# 08_eMMC.net
KiCad netlist of a schematic drawn in Altium Designer
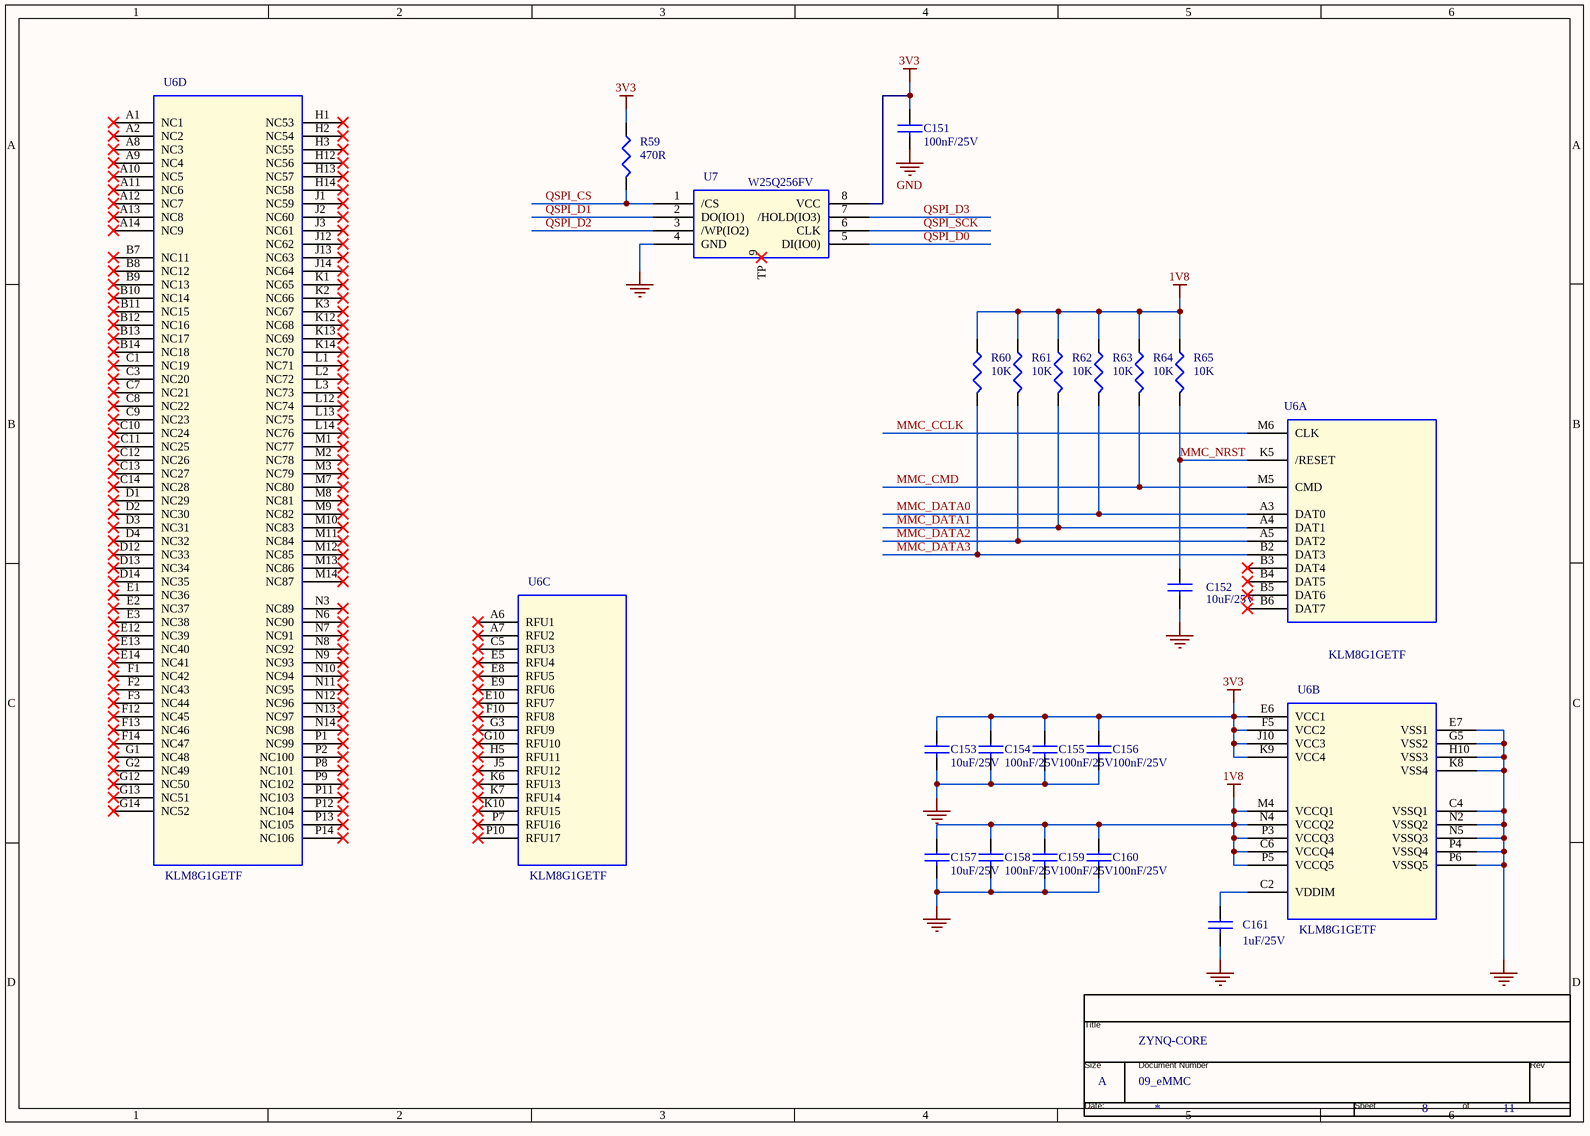
[diagram p0: 08_eMMC.SchDoc]

(export (version "E")
  (design (tool "Eeschema 10.0.6"))
  (components
    (comp (ref "C151") (value "100nF/25V") (footprint "C0402") (libsource (lib "*") (part "CAP NP")))
    (comp (ref "C152") (value "10uF/25V") (footprint "C0603") (libsource (lib "*") (part "CAP NP")))
    (comp (ref "C153") (value "10uF/25V") (footprint "C0603") (libsource (lib "*") (part "CAP NP")))
    (comp (ref "C154") (value "100nF/25V") (footprint "C0402") (libsource (lib "*") (part "CAP NP")))
    (comp (ref "C155") (value "100nF/25V") (footprint "C0402") (libsource (lib "*") (part "CAP NP")))
    (comp (ref "C156") (value "100nF/25V") (footprint "C0402") (libsource (lib "*") (part "CAP NP")))
    (comp (ref "C157") (value "10uF/25V") (footprint "C0603") (libsource (lib "*") (part "CAP NP")))
    (comp (ref "C158") (value "100nF/25V") (footprint "C0402") (libsource (lib "*") (part "CAP NP")))
    (comp (ref "C159") (value "100nF/25V") (footprint "C0402") (libsource (lib "*") (part "CAP NP")))
    (comp (ref "C160") (value "100nF/25V") (footprint "C0402") (libsource (lib "*") (part "CAP NP")))
    (comp (ref "C161") (value "1uF/25V") (footprint "C0402") (libsource (lib "*") (part "CAP NP")))
    (comp (ref "R59") (value "470R") (footprint "R0402") (libsource (lib "*") (part "RESISTOR")))
    (comp (ref "R60") (value "10K") (footprint "R0402") (libsource (lib "*") (part "RESISTOR")))
    (comp (ref "R61") (value "10K") (footprint "R0402") (libsource (lib "*") (part "RESISTOR")))
    (comp (ref "R62") (value "10K") (footprint "R0402") (libsource (lib "*") (part "RESISTOR")))
    (comp (ref "R63") (value "10K") (footprint "R0402") (libsource (lib "*") (part "RESISTOR")))
    (comp (ref "R64") (value "10K") (footprint "R0402") (libsource (lib "*") (part "RESISTOR")))
    (comp (ref "R65") (value "10K") (footprint "R0402") (libsource (lib "*") (part "RESISTOR")))
    (comp (ref "U6")
      (value "KLM8G1GETF")
      (footprint "VFBGA")
      (libsource (lib "*") (part "MTFC4GACAAAM-1M_2"))
    )
    (comp (ref "U7") (value "W25Q256FV") (footprint "MLP8") (libsource (lib "*") (part "W25Q256FV")))
  )
  (nets
    (net (code "1") (name "/MMC_CCLK") (class "Default")
      (node (ref "U6") (pin "M6") (pinfunction "CLK_M6") (pintype "passive"))
    )
    (net (code "2") (name "/MMC_CMD") (class "Default")
      (node (ref "R64") (pin "2") (pinfunction "2_2") (pintype "passive"))
      (node (ref "U6") (pin "M5") (pinfunction "CMD_M5") (pintype "passive"))
    )
    (net (code "3") (name "/MMC_DATA0") (class "Default")
      (node (ref "R63") (pin "2") (pinfunction "2_2") (pintype "passive"))
      (node (ref "U6") (pin "A3") (pinfunction "DAT0_A3") (pintype "passive"))
    )
    (net (code "4") (name "/MMC_DATA1") (class "Default")
      (node (ref "R62") (pin "2") (pinfunction "2_2") (pintype "passive"))
      (node (ref "U6") (pin "A4") (pinfunction "DAT1_A4") (pintype "passive"))
    )
    (net (code "5") (name "/MMC_DATA2") (class "Default")
      (node (ref "R61") (pin "2") (pinfunction "2_2") (pintype "passive"))
      (node (ref "U6") (pin "A5") (pinfunction "DAT2_A5") (pintype "passive"))
    )
    (net (code "6") (name "/MMC_DATA3") (class "Default")
      (node (ref "R60") (pin "2") (pinfunction "2_2") (pintype "passive"))
      (node (ref "U6") (pin "B2") (pinfunction "DAT3_B2") (pintype "passive"))
    )
    (net (code "7") (name "/MMC_NRST") (class "Default")
      (node (ref "C152") (pin "1") (pinfunction "1_1") (pintype "passive"))
      (node (ref "R65") (pin "2") (pinfunction "2_2") (pintype "passive"))
      (node (ref "U6") (pin "K5") (pinfunction "/RESET_K5") (pintype "passive"))
    )
    (net (code "8") (name "/QSPI_CS") (class "Default")
      (node (ref "R59") (pin "2") (pinfunction "2_2") (pintype "passive"))
      (node (ref "U7") (pin "1") (pinfunction "/CS_1") (pintype "passive"))
    )
    (net (code "9") (name "/QSPI_D0") (class "Default")
      (node (ref "U7") (pin "5") (pinfunction "DI(IO0)_5") (pintype "passive"))
    )
    (net (code "10") (name "/QSPI_D1") (class "Default")
      (node (ref "U7") (pin "2") (pinfunction "DO(IO1)_2") (pintype "passive"))
    )
    (net (code "11") (name "/QSPI_D2") (class "Default")
      (node (ref "U7") (pin "3") (pinfunction "/WP(IO2)_3") (pintype "passive"))
    )
    (net (code "12") (name "/QSPI_D3") (class "Default")
      (node (ref "U7") (pin "7") (pinfunction "/HOLD(IO3)_7") (pintype "passive"))
    )
    (net (code "13") (name "/QSPI_SCK") (class "Default")
      (node (ref "U7") (pin "6") (pinfunction "CLK_6") (pintype "passive"))
    )
    (net (code "14") (name "1V8") (class "Default")
      (node (ref "C157") (pin "1") (pinfunction "1_1") (pintype "passive"))
      (node (ref "C158") (pin "1") (pinfunction "1_1") (pintype "passive"))
      (node (ref "C159") (pin "1") (pinfunction "1_1") (pintype "passive"))
      (node (ref "C160") (pin "1") (pinfunction "1_1") (pintype "passive"))
      (node (ref "R60") (pin "1") (pinfunction "1_1") (pintype "passive"))
      (node (ref "R61") (pin "1") (pinfunction "1_1") (pintype "passive"))
      (node (ref "R62") (pin "1") (pinfunction "1_1") (pintype "passive"))
      (node (ref "R63") (pin "1") (pinfunction "1_1") (pintype "passive"))
      (node (ref "R64") (pin "1") (pinfunction "1_1") (pintype "passive"))
      (node (ref "R65") (pin "1") (pinfunction "1_1") (pintype "passive"))
      (node (ref "U6") (pin "C6") (pinfunction "VCCQ4_C6") (pintype "passive"))
      (node (ref "U6") (pin "M4") (pinfunction "VCCQ1_M4") (pintype "passive"))
      (node (ref "U6") (pin "N4") (pinfunction "VCCQ2_N4") (pintype "passive"))
      (node (ref "U6") (pin "P3") (pinfunction "VCCQ3_P3") (pintype "passive"))
      (node (ref "U6") (pin "P5") (pinfunction "VCCQ5_P5") (pintype "passive"))
    )
    (net (code "15") (name "3V3") (class "Default")
      (node (ref "C151") (pin "1") (pinfunction "1_1") (pintype "passive"))
      (node (ref "C153") (pin "1") (pinfunction "1_1") (pintype "passive"))
      (node (ref "C154") (pin "1") (pinfunction "1_1") (pintype "passive"))
      (node (ref "C155") (pin "1") (pinfunction "1_1") (pintype "passive"))
      (node (ref "C156") (pin "1") (pinfunction "1_1") (pintype "passive"))
      (node (ref "R59") (pin "1") (pinfunction "1_1") (pintype "passive"))
      (node (ref "U6") (pin "E6") (pinfunction "VCC1_E6") (pintype "passive"))
      (node (ref "U6") (pin "F5") (pinfunction "VCC2_F5") (pintype "passive"))
      (node (ref "U6") (pin "J10") (pinfunction "VCC3_J10") (pintype "passive"))
      (node (ref "U6") (pin "K9") (pinfunction "VCC4_K9") (pintype "passive"))
      (node (ref "U7") (pin "8") (pinfunction "VCC_8") (pintype "passive"))
    )
    (net (code "16") (name "GND") (class "Default")
      (node (ref "C151") (pin "2") (pinfunction "2_2") (pintype "passive"))
      (node (ref "C152") (pin "2") (pinfunction "2_2") (pintype "passive"))
      (node (ref "C153") (pin "2") (pinfunction "2_2") (pintype "passive"))
      (node (ref "C154") (pin "2") (pinfunction "2_2") (pintype "passive"))
      (node (ref "C155") (pin "2") (pinfunction "2_2") (pintype "passive"))
      (node (ref "C156") (pin "2") (pinfunction "2_2") (pintype "passive"))
      (node (ref "C157") (pin "2") (pinfunction "2_2") (pintype "passive"))
      (node (ref "C158") (pin "2") (pinfunction "2_2") (pintype "passive"))
      (node (ref "C159") (pin "2") (pinfunction "2_2") (pintype "passive"))
      (node (ref "C160") (pin "2") (pinfunction "2_2") (pintype "passive"))
      (node (ref "C161") (pin "2") (pinfunction "2_2") (pintype "passive"))
      (node (ref "U6") (pin "C4") (pinfunction "VSSQ1_C4") (pintype "passive"))
      (node (ref "U6") (pin "E7") (pinfunction "VSS1_E7") (pintype "passive"))
      (node (ref "U6") (pin "G5") (pinfunction "VSS2_G5") (pintype "passive"))
      (node (ref "U6") (pin "H10") (pinfunction "VSS3_H10") (pintype "passive"))
      (node (ref "U6") (pin "K8") (pinfunction "VSS4_K8") (pintype "passive"))
      (node (ref "U6") (pin "N2") (pinfunction "VSSQ2_N2") (pintype "passive"))
      (node (ref "U6") (pin "N5") (pinfunction "VSSQ3_N5") (pintype "passive"))
      (node (ref "U6") (pin "P4") (pinfunction "VSSQ4_P4") (pintype "passive"))
      (node (ref "U6") (pin "P6") (pinfunction "VSSQ5_P6") (pintype "passive"))
      (node (ref "U7") (pin "4") (pinfunction "GND_4") (pintype "passive"))
    )
    (net (code "17") (name "Net-(U6B-VDDIM)") (class "Default")
      (node (ref "C161") (pin "1") (pinfunction "1_1") (pintype "passive"))
      (node (ref "U6") (pin "C2") (pinfunction "VDDIM_C2") (pintype "passive"))
    )
    (net (code "18") (name "unconnected-(U6A-DAT4-PadB3)") (class "Default")
      (node (ref "U6") (pin "B3") (pinfunction "DAT4_B3") (pintype "passive+no_connect"))
    )
    (net (code "19") (name "unconnected-(U6A-DAT5-PadB4)") (class "Default")
      (node (ref "U6") (pin "B4") (pinfunction "DAT5_B4") (pintype "passive+no_connect"))
    )
    (net (code "20") (name "unconnected-(U6A-DAT6-PadB5)") (class "Default")
      (node (ref "U6") (pin "B5") (pinfunction "DAT6_B5") (pintype "passive+no_connect"))
    )
    (net (code "21") (name "unconnected-(U6A-DAT7-PadB6)") (class "Default")
      (node (ref "U6") (pin "B6") (pinfunction "DAT7_B6") (pintype "passive+no_connect"))
    )
    (net (code "22") (name "unconnected-(U6C-RFU1-PadA6)") (class "Default")
      (node (ref "U6") (pin "A6") (pinfunction "RFU1_A6") (pintype "passive+no_connect"))
    )
    (net (code "23") (name "unconnected-(U6C-RFU2-PadA7)") (class "Default")
      (node (ref "U6") (pin "A7") (pinfunction "RFU2_A7") (pintype "passive+no_connect"))
    )
    (net (code "24") (name "unconnected-(U6C-RFU3-PadC5)") (class "Default")
      (node (ref "U6") (pin "C5") (pinfunction "RFU3_C5") (pintype "passive+no_connect"))
    )
    (net (code "25") (name "unconnected-(U6C-RFU4-PadE5)") (class "Default")
      (node (ref "U6") (pin "E5") (pinfunction "RFU4_E5") (pintype "passive+no_connect"))
    )
    (net (code "26") (name "unconnected-(U6C-RFU5-PadE8)") (class "Default")
      (node (ref "U6") (pin "E8") (pinfunction "RFU5_E8") (pintype "passive+no_connect"))
    )
    (net (code "27") (name "unconnected-(U6C-RFU6-PadE9)") (class "Default")
      (node (ref "U6") (pin "E9") (pinfunction "RFU6_E9") (pintype "passive+no_connect"))
    )
    (net (code "28") (name "unconnected-(U6C-RFU7-PadE10)") (class "Default")
      (node (ref "U6") (pin "E10") (pinfunction "RFU7_E10") (pintype "passive+no_connect"))
    )
    (net (code "29") (name "unconnected-(U6C-RFU8-PadF10)") (class "Default")
      (node (ref "U6") (pin "F10") (pinfunction "RFU8_F10") (pintype "passive+no_connect"))
    )
    (net (code "30") (name "unconnected-(U6C-RFU9-PadG3)") (class "Default")
      (node (ref "U6") (pin "G3") (pinfunction "RFU9_G3") (pintype "passive+no_connect"))
    )
    (net (code "31") (name "unconnected-(U6C-RFU10-PadG10)") (class "Default")
      (node (ref "U6") (pin "G10") (pinfunction "RFU10_G10") (pintype "passive+no_connect"))
    )
    (net (code "32") (name "unconnected-(U6C-RFU11-PadH5)") (class "Default")
      (node (ref "U6") (pin "H5") (pinfunction "RFU11_H5") (pintype "passive+no_connect"))
    )
    (net (code "33") (name "unconnected-(U6C-RFU12-PadJ5)") (class "Default")
      (node (ref "U6") (pin "J5") (pinfunction "RFU12_J5") (pintype "passive+no_connect"))
    )
    (net (code "34") (name "unconnected-(U6C-RFU13-PadK6)") (class "Default")
      (node (ref "U6") (pin "K6") (pinfunction "RFU13_K6") (pintype "passive+no_connect"))
    )
    (net (code "35") (name "unconnected-(U6C-RFU14-PadK7)") (class "Default")
      (node (ref "U6") (pin "K7") (pinfunction "RFU14_K7") (pintype "passive+no_connect"))
    )
    (net (code "36") (name "unconnected-(U6C-RFU15-PadK10)") (class "Default")
      (node (ref "U6") (pin "K10") (pinfunction "RFU15_K10") (pintype "passive+no_connect"))
    )
    (net (code "37") (name "unconnected-(U6C-RFU16-PadP7)") (class "Default")
      (node (ref "U6") (pin "P7") (pinfunction "RFU16_P7") (pintype "passive+no_connect"))
    )
    (net (code "38") (name "unconnected-(U6C-RFU17-PadP10)") (class "Default")
      (node (ref "U6") (pin "P10") (pinfunction "RFU17_P10") (pintype "passive+no_connect"))
    )
    (net (code "39") (name "unconnected-(U6D-NC1-PadA1)") (class "Default")
      (node (ref "U6") (pin "A1") (pinfunction "NC1_A1") (pintype "passive+no_connect"))
    )
    (net (code "40") (name "unconnected-(U6D-NC2-PadA2)") (class "Default")
      (node (ref "U6") (pin "A2") (pinfunction "NC2_A2") (pintype "passive+no_connect"))
    )
    (net (code "41") (name "unconnected-(U6D-NC3-PadA8)") (class "Default")
      (node (ref "U6") (pin "A8") (pinfunction "NC3_A8") (pintype "passive+no_connect"))
    )
    (net (code "42") (name "unconnected-(U6D-NC4-PadA9)") (class "Default")
      (node (ref "U6") (pin "A9") (pinfunction "NC4_A9") (pintype "passive+no_connect"))
    )
    (net (code "43") (name "unconnected-(U6D-NC5-PadA10)") (class "Default")
      (node (ref "U6") (pin "A10") (pinfunction "NC5_A10") (pintype "passive+no_connect"))
    )
    (net (code "44") (name "unconnected-(U6D-NC6-PadA11)") (class "Default")
      (node (ref "U6") (pin "A11") (pinfunction "NC6_A11") (pintype "passive+no_connect"))
    )
    (net (code "45") (name "unconnected-(U6D-NC7-PadA12)") (class "Default")
      (node (ref "U6") (pin "A12") (pinfunction "NC7_A12") (pintype "passive+no_connect"))
    )
    (net (code "46") (name "unconnected-(U6D-NC8-PadA13)") (class "Default")
      (node (ref "U6") (pin "A13") (pinfunction "NC8_A13") (pintype "passive+no_connect"))
    )
    (net (code "47") (name "unconnected-(U6D-NC9-PadA14)") (class "Default")
      (node (ref "U6") (pin "A14") (pinfunction "NC9_A14") (pintype "passive+no_connect"))
    )
    (net (code "48") (name "unconnected-(U6D-NC11-PadB7)") (class "Default")
      (node (ref "U6") (pin "B7") (pinfunction "NC11_B7") (pintype "passive+no_connect"))
    )
    (net (code "49") (name "unconnected-(U6D-NC12-PadB8)") (class "Default")
      (node (ref "U6") (pin "B8") (pinfunction "NC12_B8") (pintype "passive+no_connect"))
    )
    (net (code "50") (name "unconnected-(U6D-NC13-PadB9)") (class "Default")
      (node (ref "U6") (pin "B9") (pinfunction "NC13_B9") (pintype "passive+no_connect"))
    )
    (net (code "51") (name "unconnected-(U6D-NC14-PadB10)") (class "Default")
      (node (ref "U6") (pin "B10") (pinfunction "NC14_B10") (pintype "passive+no_connect"))
    )
    (net (code "52") (name "unconnected-(U6D-NC15-PadB11)") (class "Default")
      (node (ref "U6") (pin "B11") (pinfunction "NC15_B11") (pintype "passive+no_connect"))
    )
    (net (code "53") (name "unconnected-(U6D-NC16-PadB12)") (class "Default")
      (node (ref "U6") (pin "B12") (pinfunction "NC16_B12") (pintype "passive+no_connect"))
    )
    (net (code "54") (name "unconnected-(U6D-NC17-PadB13)") (class "Default")
      (node (ref "U6") (pin "B13") (pinfunction "NC17_B13") (pintype "passive+no_connect"))
    )
    (net (code "55") (name "unconnected-(U6D-NC18-PadB14)") (class "Default")
      (node (ref "U6") (pin "B14") (pinfunction "NC18_B14") (pintype "passive+no_connect"))
    )
    (net (code "56") (name "unconnected-(U6D-NC19-PadC1)") (class "Default")
      (node (ref "U6") (pin "C1") (pinfunction "NC19_C1") (pintype "passive+no_connect"))
    )
    (net (code "57") (name "unconnected-(U6D-NC20-PadC3)") (class "Default")
      (node (ref "U6") (pin "C3") (pinfunction "NC20_C3") (pintype "passive+no_connect"))
    )
    (net (code "58") (name "unconnected-(U6D-NC21-PadC7)") (class "Default")
      (node (ref "U6") (pin "C7") (pinfunction "NC21_C7") (pintype "passive+no_connect"))
    )
    (net (code "59") (name "unconnected-(U6D-NC22-PadC8)") (class "Default")
      (node (ref "U6") (pin "C8") (pinfunction "NC22_C8") (pintype "passive+no_connect"))
    )
    (net (code "60") (name "unconnected-(U6D-NC23-PadC9)") (class "Default")
      (node (ref "U6") (pin "C9") (pinfunction "NC23_C9") (pintype "passive+no_connect"))
    )
    (net (code "61") (name "unconnected-(U6D-NC24-PadC10)") (class "Default")
      (node (ref "U6") (pin "C10") (pinfunction "NC24_C10") (pintype "passive+no_connect"))
    )
    (net (code "62") (name "unconnected-(U6D-NC25-PadC11)") (class "Default")
      (node (ref "U6") (pin "C11") (pinfunction "NC25_C11") (pintype "passive+no_connect"))
    )
    (net (code "63") (name "unconnected-(U6D-NC26-PadC12)") (class "Default")
      (node (ref "U6") (pin "C12") (pinfunction "NC26_C12") (pintype "passive+no_connect"))
    )
    (net (code "64") (name "unconnected-(U6D-NC27-PadC13)") (class "Default")
      (node (ref "U6") (pin "C13") (pinfunction "NC27_C13") (pintype "passive+no_connect"))
    )
    (net (code "65") (name "unconnected-(U6D-NC28-PadC14)") (class "Default")
      (node (ref "U6") (pin "C14") (pinfunction "NC28_C14") (pintype "passive+no_connect"))
    )
    (net (code "66") (name "unconnected-(U6D-NC29-PadD1)") (class "Default")
      (node (ref "U6") (pin "D1") (pinfunction "NC29_D1") (pintype "passive+no_connect"))
    )
    (net (code "67") (name "unconnected-(U6D-NC30-PadD2)") (class "Default")
      (node (ref "U6") (pin "D2") (pinfunction "NC30_D2") (pintype "passive+no_connect"))
    )
    (net (code "68") (name "unconnected-(U6D-NC31-PadD3)") (class "Default")
      (node (ref "U6") (pin "D3") (pinfunction "NC31_D3") (pintype "passive+no_connect"))
    )
    (net (code "69") (name "unconnected-(U6D-NC32-PadD4)") (class "Default")
      (node (ref "U6") (pin "D4") (pinfunction "NC32_D4") (pintype "passive+no_connect"))
    )
    (net (code "70") (name "unconnected-(U6D-NC33-PadD12)") (class "Default")
      (node (ref "U6") (pin "D12") (pinfunction "NC33_D12") (pintype "passive+no_connect"))
    )
    (net (code "71") (name "unconnected-(U6D-NC34-PadD13)") (class "Default")
      (node (ref "U6") (pin "D13") (pinfunction "NC34_D13") (pintype "passive+no_connect"))
    )
    (net (code "72") (name "unconnected-(U6D-NC35-PadD14)") (class "Default")
      (node (ref "U6") (pin "D14") (pinfunction "NC35_D14") (pintype "passive+no_connect"))
    )
    (net (code "73") (name "unconnected-(U6D-NC36-PadE1)") (class "Default")
      (node (ref "U6") (pin "E1") (pinfunction "NC36_E1") (pintype "passive+no_connect"))
    )
    (net (code "74") (name "unconnected-(U6D-NC37-PadE2)") (class "Default")
      (node (ref "U6") (pin "E2") (pinfunction "NC37_E2") (pintype "passive+no_connect"))
    )
    (net (code "75") (name "unconnected-(U6D-NC38-PadE3)") (class "Default")
      (node (ref "U6") (pin "E3") (pinfunction "NC38_E3") (pintype "passive+no_connect"))
    )
    (net (code "76") (name "unconnected-(U6D-NC39-PadE12)") (class "Default")
      (node (ref "U6") (pin "E12") (pinfunction "NC39_E12") (pintype "passive+no_connect"))
    )
    (net (code "77") (name "unconnected-(U6D-NC40-PadE13)") (class "Default")
      (node (ref "U6") (pin "E13") (pinfunction "NC40_E13") (pintype "passive+no_connect"))
    )
    (net (code "78") (name "unconnected-(U6D-NC41-PadE14)") (class "Default")
      (node (ref "U6") (pin "E14") (pinfunction "NC41_E14") (pintype "passive+no_connect"))
    )
    (net (code "79") (name "unconnected-(U6D-NC42-PadF1)") (class "Default")
      (node (ref "U6") (pin "F1") (pinfunction "NC42_F1") (pintype "passive+no_connect"))
    )
    (net (code "80") (name "unconnected-(U6D-NC43-PadF2)") (class "Default")
      (node (ref "U6") (pin "F2") (pinfunction "NC43_F2") (pintype "passive+no_connect"))
    )
    (net (code "81") (name "unconnected-(U6D-NC44-PadF3)") (class "Default")
      (node (ref "U6") (pin "F3") (pinfunction "NC44_F3") (pintype "passive+no_connect"))
    )
    (net (code "82") (name "unconnected-(U6D-NC45-PadF12)") (class "Default")
      (node (ref "U6") (pin "F12") (pinfunction "NC45_F12") (pintype "passive+no_connect"))
    )
    (net (code "83") (name "unconnected-(U6D-NC46-PadF13)") (class "Default")
      (node (ref "U6") (pin "F13") (pinfunction "NC46_F13") (pintype "passive+no_connect"))
    )
    (net (code "84") (name "unconnected-(U6D-NC47-PadF14)") (class "Default")
      (node (ref "U6") (pin "F14") (pinfunction "NC47_F14") (pintype "passive+no_connect"))
    )
    (net (code "85") (name "unconnected-(U6D-NC48-PadG1)") (class "Default")
      (node (ref "U6") (pin "G1") (pinfunction "NC48_G1") (pintype "passive+no_connect"))
    )
    (net (code "86") (name "unconnected-(U6D-NC49-PadG2)") (class "Default")
      (node (ref "U6") (pin "G2") (pinfunction "NC49_G2") (pintype "passive+no_connect"))
    )
    (net (code "87") (name "unconnected-(U6D-NC50-PadG12)") (class "Default")
      (node (ref "U6") (pin "G12") (pinfunction "NC50_G12") (pintype "passive+no_connect"))
    )
    (net (code "88") (name "unconnected-(U6D-NC51-PadG13)") (class "Default")
      (node (ref "U6") (pin "G13") (pinfunction "NC51_G13") (pintype "passive+no_connect"))
    )
    (net (code "89") (name "unconnected-(U6D-NC52-PadG14)") (class "Default")
      (node (ref "U6") (pin "G14") (pinfunction "NC52_G14") (pintype "passive+no_connect"))
    )
    (net (code "90") (name "unconnected-(U6D-NC53-PadH1)") (class "Default")
      (node (ref "U6") (pin "H1") (pinfunction "NC53_H1") (pintype "passive+no_connect"))
    )
    (net (code "91") (name "unconnected-(U6D-NC54-PadH2)") (class "Default")
      (node (ref "U6") (pin "H2") (pinfunction "NC54_H2") (pintype "passive+no_connect"))
    )
    (net (code "92") (name "unconnected-(U6D-NC55-PadH3)") (class "Default")
      (node (ref "U6") (pin "H3") (pinfunction "NC55_H3") (pintype "passive+no_connect"))
    )
    (net (code "93") (name "unconnected-(U6D-NC56-PadH12)") (class "Default")
      (node (ref "U6") (pin "H12") (pinfunction "NC56_H12") (pintype "passive+no_connect"))
    )
    (net (code "94") (name "unconnected-(U6D-NC57-PadH13)") (class "Default")
      (node (ref "U6") (pin "H13") (pinfunction "NC57_H13") (pintype "passive+no_connect"))
    )
    (net (code "95") (name "unconnected-(U6D-NC58-PadH14)") (class "Default")
      (node (ref "U6") (pin "H14") (pinfunction "NC58_H14") (pintype "passive+no_connect"))
    )
    (net (code "96") (name "unconnected-(U6D-NC59-PadJ1)") (class "Default")
      (node (ref "U6") (pin "J1") (pinfunction "NC59_J1") (pintype "passive+no_connect"))
    )
    (net (code "97") (name "unconnected-(U6D-NC60-PadJ2)") (class "Default")
      (node (ref "U6") (pin "J2") (pinfunction "NC60_J2") (pintype "passive+no_connect"))
    )
    (net (code "98") (name "unconnected-(U6D-NC61-PadJ3)") (class "Default")
      (node (ref "U6") (pin "J3") (pinfunction "NC61_J3") (pintype "passive+no_connect"))
    )
    (net (code "99") (name "unconnected-(U6D-NC62-PadJ12)") (class "Default")
      (node (ref "U6") (pin "J12") (pinfunction "NC62_J12") (pintype "passive+no_connect"))
    )
    (net (code "100") (name "unconnected-(U6D-NC63-PadJ13)") (class "Default")
      (node (ref "U6") (pin "J13") (pinfunction "NC63_J13") (pintype "passive+no_connect"))
    )
    (net (code "101") (name "unconnected-(U6D-NC64-PadJ14)") (class "Default")
      (node (ref "U6") (pin "J14") (pinfunction "NC64_J14") (pintype "passive+no_connect"))
    )
    (net (code "102") (name "unconnected-(U6D-NC65-PadK1)") (class "Default")
      (node (ref "U6") (pin "K1") (pinfunction "NC65_K1") (pintype "passive+no_connect"))
    )
    (net (code "103") (name "unconnected-(U6D-NC66-PadK2)") (class "Default")
      (node (ref "U6") (pin "K2") (pinfunction "NC66_K2") (pintype "passive+no_connect"))
    )
    (net (code "104") (name "unconnected-(U6D-NC67-PadK3)") (class "Default")
      (node (ref "U6") (pin "K3") (pinfunction "NC67_K3") (pintype "passive+no_connect"))
    )
    (net (code "105") (name "unconnected-(U6D-NC68-PadK12)") (class "Default")
      (node (ref "U6") (pin "K12") (pinfunction "NC68_K12") (pintype "passive+no_connect"))
    )
    (net (code "106") (name "unconnected-(U6D-NC69-PadK13)") (class "Default")
      (node (ref "U6") (pin "K13") (pinfunction "NC69_K13") (pintype "passive+no_connect"))
    )
    (net (code "107") (name "unconnected-(U6D-NC70-PadK14)") (class "Default")
      (node (ref "U6") (pin "K14") (pinfunction "NC70_K14") (pintype "passive+no_connect"))
    )
    (net (code "108") (name "unconnected-(U6D-NC71-PadL1)") (class "Default")
      (node (ref "U6") (pin "L1") (pinfunction "NC71_L1") (pintype "passive+no_connect"))
    )
    (net (code "109") (name "unconnected-(U6D-NC72-PadL2)") (class "Default")
      (node (ref "U6") (pin "L2") (pinfunction "NC72_L2") (pintype "passive+no_connect"))
    )
    (net (code "110") (name "unconnected-(U6D-NC73-PadL3)") (class "Default")
      (node (ref "U6") (pin "L3") (pinfunction "NC73_L3") (pintype "passive+no_connect"))
    )
    (net (code "111") (name "unconnected-(U6D-NC74-PadL12)") (class "Default")
      (node (ref "U6") (pin "L12") (pinfunction "NC74_L12") (pintype "passive+no_connect"))
    )
    (net (code "112") (name "unconnected-(U6D-NC75-PadL13)") (class "Default")
      (node (ref "U6") (pin "L13") (pinfunction "NC75_L13") (pintype "passive+no_connect"))
    )
    (net (code "113") (name "unconnected-(U6D-NC76-PadL14)") (class "Default")
      (node (ref "U6") (pin "L14") (pinfunction "NC76_L14") (pintype "passive+no_connect"))
    )
    (net (code "114") (name "unconnected-(U6D-NC77-PadM1)") (class "Default")
      (node (ref "U6") (pin "M1") (pinfunction "NC77_M1") (pintype "passive+no_connect"))
    )
    (net (code "115") (name "unconnected-(U6D-NC78-PadM2)") (class "Default")
      (node (ref "U6") (pin "M2") (pinfunction "NC78_M2") (pintype "passive+no_connect"))
    )
    (net (code "116") (name "unconnected-(U6D-NC79-PadM3)") (class "Default")
      (node (ref "U6") (pin "M3") (pinfunction "NC79_M3") (pintype "passive+no_connect"))
    )
    (net (code "117") (name "unconnected-(U6D-NC80-PadM7)") (class "Default")
      (node (ref "U6") (pin "M7") (pinfunction "NC80_M7") (pintype "passive+no_connect"))
    )
    (net (code "118") (name "unconnected-(U6D-NC81-PadM8)") (class "Default")
      (node (ref "U6") (pin "M8") (pinfunction "NC81_M8") (pintype "passive+no_connect"))
    )
    (net (code "119") (name "unconnected-(U6D-NC82-PadM9)") (class "Default")
      (node (ref "U6") (pin "M9") (pinfunction "NC82_M9") (pintype "passive+no_connect"))
    )
    (net (code "120") (name "unconnected-(U6D-NC83-PadM10)") (class "Default")
      (node (ref "U6") (pin "M10") (pinfunction "NC83_M10") (pintype "passive+no_connect"))
    )
    (net (code "121") (name "unconnected-(U6D-NC84-PadM11)") (class "Default")
      (node (ref "U6") (pin "M11") (pinfunction "NC84_M11") (pintype "passive+no_connect"))
    )
    (net (code "122") (name "unconnected-(U6D-NC85-PadM12)") (class "Default")
      (node (ref "U6") (pin "M12") (pinfunction "NC85_M12") (pintype "passive+no_connect"))
    )
    (net (code "123") (name "unconnected-(U6D-NC86-PadM13)") (class "Default")
      (node (ref "U6") (pin "M13") (pinfunction "NC86_M13") (pintype "passive+no_connect"))
    )
    (net (code "124") (name "unconnected-(U6D-NC87-PadM14)") (class "Default")
      (node (ref "U6") (pin "M14") (pinfunction "NC87_M14") (pintype "passive+no_connect"))
    )
    (net (code "125") (name "unconnected-(U6D-NC89-PadN3)") (class "Default")
      (node (ref "U6") (pin "N3") (pinfunction "NC89_N3") (pintype "passive+no_connect"))
    )
    (net (code "126") (name "unconnected-(U6D-NC90-PadN6)") (class "Default")
      (node (ref "U6") (pin "N6") (pinfunction "NC90_N6") (pintype "passive+no_connect"))
    )
    (net (code "127") (name "unconnected-(U6D-NC91-PadN7)") (class "Default")
      (node (ref "U6") (pin "N7") (pinfunction "NC91_N7") (pintype "passive+no_connect"))
    )
    (net (code "128") (name "unconnected-(U6D-NC92-PadN8)") (class "Default")
      (node (ref "U6") (pin "N8") (pinfunction "NC92_N8") (pintype "passive+no_connect"))
    )
    (net (code "129") (name "unconnected-(U6D-NC93-PadN9)") (class "Default")
      (node (ref "U6") (pin "N9") (pinfunction "NC93_N9") (pintype "passive+no_connect"))
    )
    (net (code "130") (name "unconnected-(U6D-NC94-PadN10)") (class "Default")
      (node (ref "U6") (pin "N10") (pinfunction "NC94_N10") (pintype "passive+no_connect"))
    )
    (net (code "131") (name "unconnected-(U6D-NC95-PadN11)") (class "Default")
      (node (ref "U6") (pin "N11") (pinfunction "NC95_N11") (pintype "passive+no_connect"))
    )
    (net (code "132") (name "unconnected-(U6D-NC96-PadN12)") (class "Default")
      (node (ref "U6") (pin "N12") (pinfunction "NC96_N12") (pintype "passive+no_connect"))
    )
    (net (code "133") (name "unconnected-(U6D-NC97-PadN13)") (class "Default")
      (node (ref "U6") (pin "N13") (pinfunction "NC97_N13") (pintype "passive+no_connect"))
    )
    (net (code "134") (name "unconnected-(U6D-NC98-PadN14)") (class "Default")
      (node (ref "U6") (pin "N14") (pinfunction "NC98_N14") (pintype "passive+no_connect"))
    )
    (net (code "135") (name "unconnected-(U6D-NC99-PadP1)") (class "Default")
      (node (ref "U6") (pin "P1") (pinfunction "NC99_P1") (pintype "passive+no_connect"))
    )
    (net (code "136") (name "unconnected-(U6D-NC100-PadP2)") (class "Default")
      (node (ref "U6") (pin "P2") (pinfunction "NC100_P2") (pintype "passive+no_connect"))
    )
    (net (code "137") (name "unconnected-(U6D-NC101-PadP8)") (class "Default")
      (node (ref "U6") (pin "P8") (pinfunction "NC101_P8") (pintype "passive+no_connect"))
    )
    (net (code "138") (name "unconnected-(U6D-NC102-PadP9)") (class "Default")
      (node (ref "U6") (pin "P9") (pinfunction "NC102_P9") (pintype "passive+no_connect"))
    )
    (net (code "139") (name "unconnected-(U6D-NC103-PadP11)") (class "Default")
      (node (ref "U6") (pin "P11") (pinfunction "NC103_P11") (pintype "passive+no_connect"))
    )
    (net (code "140") (name "unconnected-(U6D-NC104-PadP12)") (class "Default")
      (node (ref "U6") (pin "P12") (pinfunction "NC104_P12") (pintype "passive+no_connect"))
    )
    (net (code "141") (name "unconnected-(U6D-NC105-PadP13)") (class "Default")
      (node (ref "U6") (pin "P13") (pinfunction "NC105_P13") (pintype "passive+no_connect"))
    )
    (net (code "142") (name "unconnected-(U6D-NC106-PadP14)") (class "Default")
      (node (ref "U6") (pin "P14") (pinfunction "NC106_P14") (pintype "passive+no_connect"))
    )
    (net (code "143") (name "unconnected-(U7-TP-Pad9)") (class "Default")
      (node (ref "U7") (pin "9") (pinfunction "TP_9") (pintype "passive+no_connect"))
    )
  )
)
